# lab_fisica.net
KiCad netlist of a schematic drawn in EAGLE
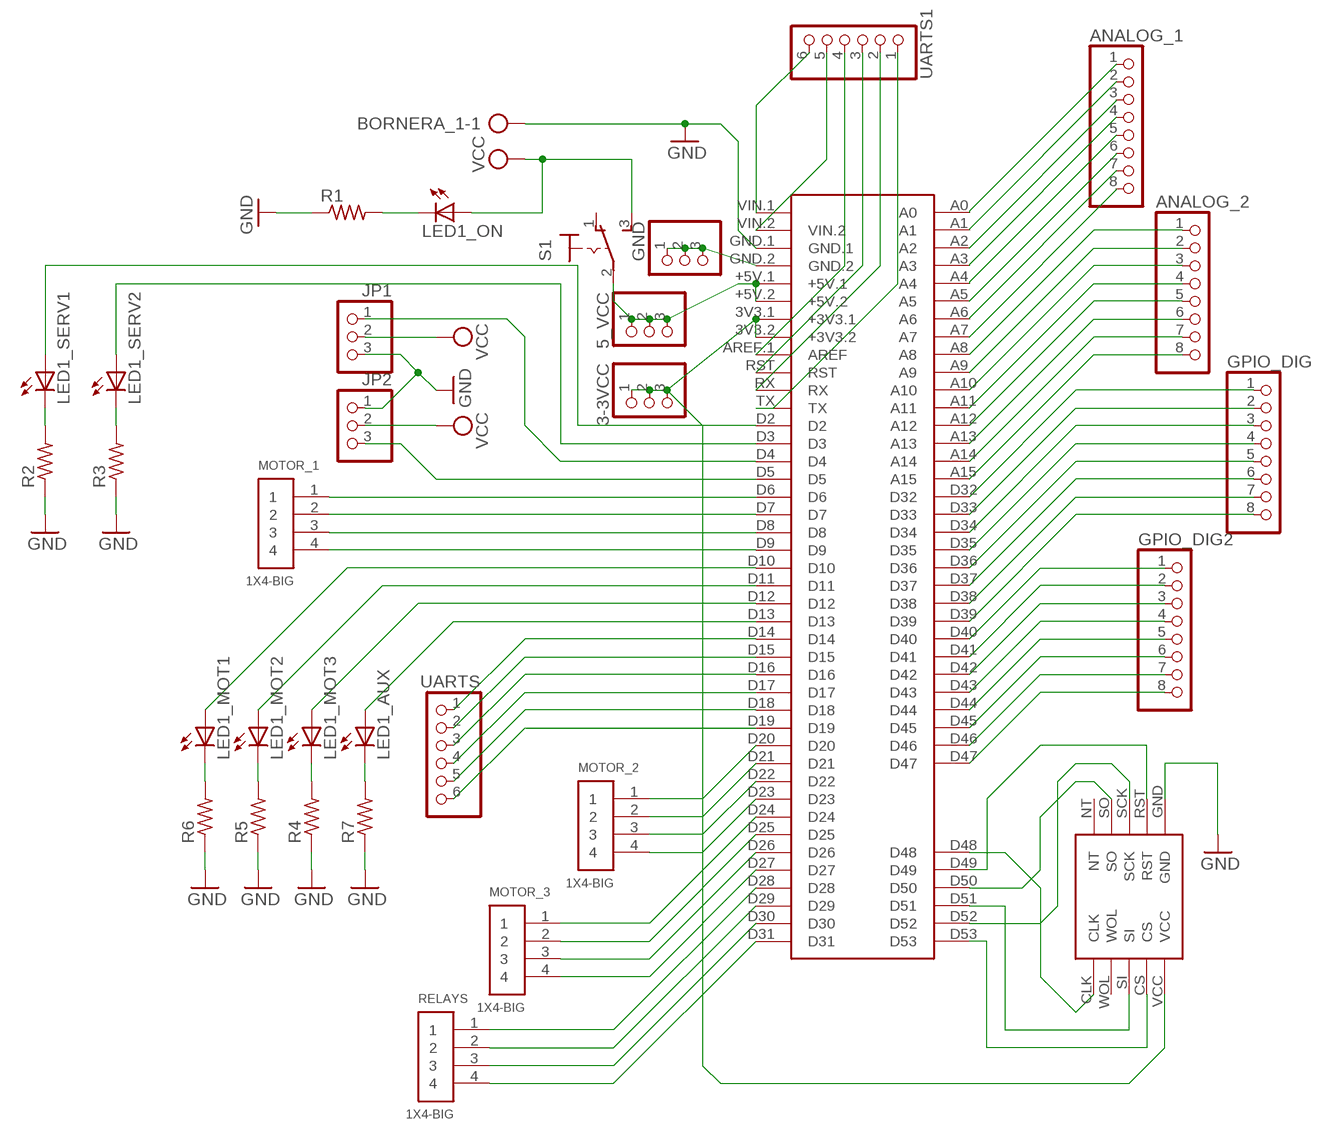
[diagram p0: schematic, sheet 1]

(export (version "E")
  (design (tool "Eeschema 10.0.6"))
  (components
    (comp (ref "3-3VCC")
      (value "PINHD-1X3")
      (footprint "eagle-import:1X03")
      (libsource (lib "eagle-import") (part "PINHD-1X3"))
    )
    (comp (ref "5_VCC")
      (value "PINHD-1X3")
      (footprint "eagle-import:1X03")
      (libsource (lib "eagle-import") (part "PINHD-1X3"))
    )
    (comp (ref "ANALOG_1")
      (value "PINHD-1X8BIG")
      (footprint "eagle-import:1X08-BIG")
      (libsource (lib "eagle-import") (part "PINHD-1X8BIG"))
    )
    (comp (ref "ANALOG_2")
      (value "PINHD-1X8BIG")
      (footprint "eagle-import:1X08-BIG")
      (libsource (lib "eagle-import") (part "PINHD-1X8BIG"))
    )
    (comp (ref "BORNERA_1")
      (value "AK300/2")
      (footprint "eagle-import:AK300_2")
      (libsource (lib "eagle-import") (part "AK300/2"))
    )
    (comp (ref "GND")
      (value "PINHD-1X3")
      (footprint "eagle-import:1X03")
      (libsource (lib "eagle-import") (part "PINHD-1X3"))
    )
    (comp (ref "GPIO_DIG")
      (value "PINHD-1X8BIG")
      (footprint "eagle-import:1X08-BIG")
      (libsource (lib "eagle-import") (part "PINHD-1X8BIG"))
    )
    (comp (ref "GPIO_DIG2")
      (value "PINHD-1X8BIG")
      (footprint "eagle-import:1X08-BIG")
      (libsource (lib "eagle-import") (part "PINHD-1X8BIG"))
    )
    (comp (ref "JP1")
      (value "PINHD-1X3")
      (footprint "eagle-import:1X03")
      (libsource (lib "eagle-import") (part "PINHD-1X3"))
    )
    (comp (ref "JP2")
      (value "PINHD-1X3")
      (footprint "eagle-import:1X03")
      (libsource (lib "eagle-import") (part "PINHD-1X3"))
    )
    (comp (ref "LED1_AUX")
      (value "LED5MM")
      (footprint "eagle-import:LED5MM")
      (libsource (lib "eagle-import") (part "LED5MM"))
    )
    (comp (ref "LED1_MOT1")
      (value "LED5MM")
      (footprint "eagle-import:LED5MM")
      (libsource (lib "eagle-import") (part "LED5MM"))
    )
    (comp (ref "LED1_MOT2")
      (value "LED5MM")
      (footprint "eagle-import:LED5MM")
      (libsource (lib "eagle-import") (part "LED5MM"))
    )
    (comp (ref "LED1_MOT3")
      (value "LED5MM")
      (footprint "eagle-import:LED5MM")
      (libsource (lib "eagle-import") (part "LED5MM"))
    )
    (comp (ref "LED1_ON")
      (value "LED5MM")
      (footprint "eagle-import:LED5MM")
      (libsource (lib "eagle-import") (part "LED5MM"))
    )
    (comp (ref "LED1_SERV1")
      (value "LED5MM")
      (footprint "eagle-import:LED5MM")
      (libsource (lib "eagle-import") (part "LED5MM"))
    )
    (comp (ref "LED1_SERV2")
      (value "LED5MM")
      (footprint "eagle-import:LED5MM")
      (libsource (lib "eagle-import") (part "LED5MM"))
    )
    (comp (ref "MODULO_ETHERNET")
      (value "ENC28J60")
      (footprint "eagle-import:ENC28J60")
      (libsource (lib "eagle-import") (part "ENC28J60"))
    )
    (comp (ref "MOTOR_1")
      (value "1X4-BIG")
      (footprint "eagle-import:1X04-BIG")
      (libsource (lib "eagle-import") (part "1X4-BIG"))
    )
    (comp (ref "MOTOR_2")
      (value "1X4-BIG")
      (footprint "eagle-import:1X04-BIG")
      (libsource (lib "eagle-import") (part "1X4-BIG"))
    )
    (comp (ref "MOTOR_3")
      (value "1X4-BIG")
      (footprint "eagle-import:1X04-BIG")
      (libsource (lib "eagle-import") (part "1X4-BIG"))
    )
    (comp (ref "R1")
      (value "R-US_R0805")
      (footprint "eagle-import:R0805")
      (libsource (lib "eagle-import") (part "R-US_R0805"))
    )
    (comp (ref "R2")
      (value "R-US_R0805")
      (footprint "eagle-import:R0805")
      (libsource (lib "eagle-import") (part "R-US_R0805"))
    )
    (comp (ref "R3")
      (value "R-US_R0805")
      (footprint "eagle-import:R0805")
      (libsource (lib "eagle-import") (part "R-US_R0805"))
    )
    (comp (ref "R4")
      (value "R-US_R0805")
      (footprint "eagle-import:R0805")
      (libsource (lib "eagle-import") (part "R-US_R0805"))
    )
    (comp (ref "R5")
      (value "R-US_R0805")
      (footprint "eagle-import:R0805")
      (libsource (lib "eagle-import") (part "R-US_R0805"))
    )
    (comp (ref "R6")
      (value "R-US_R0805")
      (footprint "eagle-import:R0805")
      (libsource (lib "eagle-import") (part "R-US_R0805"))
    )
    (comp (ref "R7")
      (value "R-US_R0805")
      (footprint "eagle-import:R0805")
      (libsource (lib "eagle-import") (part "R-US_R0805"))
    )
    (comp (ref "RELAYS")
      (value "1X4-BIG")
      (footprint "eagle-import:1X04-BIG")
      (libsource (lib "eagle-import") (part "1X4-BIG"))
    )
    (comp (ref "S1")
      (value "320-916")
      (footprint "eagle-import:320-916")
      (libsource (lib "eagle-import") (part "320-916"))
    )
    (comp (ref "U$1")
      (value "MEGA2560_MIKRO")
      (footprint "eagle-import:MEGA2560_MIKRO")
      (libsource (lib "eagle-import") (part "MEGA2560_MIKRO"))
    )
    (comp (ref "UARTS")
      (value "PINHD-1X6B")
      (footprint "eagle-import:1X06-BIG")
      (libsource (lib "eagle-import") (part "PINHD-1X6B"))
    )
    (comp (ref "UARTS1")
      (value "PINHD-1X6B")
      (footprint "eagle-import:1X06-BIG")
      (libsource (lib "eagle-import") (part "PINHD-1X6B"))
    )
  )
  (nets
    (net (code "1") (name "GND") (class "Default")
      (node (ref "BORNERA_1") (pin "1") (pinfunction "KL_1") (pintype "passive"))
      (node (ref "JP1") (pin "3") (pinfunction "3_3") (pintype "passive"))
      (node (ref "JP2") (pin "1") (pinfunction "1_1") (pintype "passive"))
      (node (ref "MODULO_ETHERNET") (pin "GND") (pinfunction "GND_GND") (pintype "bidirectional"))
      (node (ref "R1") (pin "1") (pinfunction "1_1") (pintype "passive"))
      (node (ref "R2") (pin "1") (pinfunction "1_1") (pintype "passive"))
      (node (ref "R3") (pin "1") (pinfunction "1_1") (pintype "passive"))
      (node (ref "R4") (pin "1") (pinfunction "1_1") (pintype "passive"))
      (node (ref "R5") (pin "1") (pinfunction "1_1") (pintype "passive"))
      (node (ref "R6") (pin "1") (pinfunction "1_1") (pintype "passive"))
      (node (ref "R7") (pin "1") (pinfunction "1_1") (pintype "passive"))
      (node (ref "U$1") (pin "GND.1") (pinfunction "GND.1_GND.1") (pintype "bidirectional"))
    )
    (net (code "2") (name "Net-(ANALOG_1-Pad1)") (class "Default")
      (node (ref "ANALOG_1") (pin "1") (pinfunction "1_1") (pintype "passive"))
      (node (ref "U$1") (pin "A0") (pinfunction "A0_A0") (pintype "bidirectional"))
    )
    (net (code "3") (name "Net-(ANALOG_1-Pad2)") (class "Default")
      (node (ref "ANALOG_1") (pin "2") (pinfunction "2_2") (pintype "passive"))
      (node (ref "U$1") (pin "A1") (pinfunction "A1_A1") (pintype "bidirectional"))
    )
    (net (code "4") (name "Net-(ANALOG_1-Pad3)") (class "Default")
      (node (ref "ANALOG_1") (pin "3") (pinfunction "3_3") (pintype "passive"))
      (node (ref "U$1") (pin "A2") (pinfunction "A2_A2") (pintype "bidirectional"))
    )
    (net (code "5") (name "Net-(ANALOG_1-Pad4)") (class "Default")
      (node (ref "ANALOG_1") (pin "4") (pinfunction "4_4") (pintype "passive"))
      (node (ref "U$1") (pin "A3") (pinfunction "A3_A3") (pintype "bidirectional"))
    )
    (net (code "6") (name "Net-(ANALOG_1-Pad5)") (class "Default")
      (node (ref "ANALOG_1") (pin "5") (pinfunction "5_5") (pintype "passive"))
      (node (ref "U$1") (pin "A4") (pinfunction "A4_A4") (pintype "bidirectional"))
    )
    (net (code "7") (name "Net-(ANALOG_1-Pad6)") (class "Default")
      (node (ref "ANALOG_1") (pin "6") (pinfunction "6_6") (pintype "passive"))
      (node (ref "U$1") (pin "A5") (pinfunction "A5_A5") (pintype "bidirectional"))
    )
    (net (code "8") (name "Net-(ANALOG_1-Pad7)") (class "Default")
      (node (ref "ANALOG_1") (pin "7") (pinfunction "7_7") (pintype "passive"))
      (node (ref "U$1") (pin "A6") (pinfunction "A6_A6") (pintype "bidirectional"))
    )
    (net (code "9") (name "Net-(ANALOG_1-Pad8)") (class "Default")
      (node (ref "ANALOG_1") (pin "8") (pinfunction "8_8") (pintype "passive"))
      (node (ref "U$1") (pin "A7") (pinfunction "A7_A7") (pintype "bidirectional"))
    )
    (net (code "10") (name "Net-(ANALOG_2-Pad1)") (class "Default")
      (node (ref "ANALOG_2") (pin "1") (pinfunction "1_1") (pintype "passive"))
      (node (ref "U$1") (pin "A8") (pinfunction "A8_A8") (pintype "bidirectional"))
    )
    (net (code "11") (name "Net-(ANALOG_2-Pad2)") (class "Default")
      (node (ref "ANALOG_2") (pin "2") (pinfunction "2_2") (pintype "passive"))
      (node (ref "U$1") (pin "A9") (pinfunction "A9_A9") (pintype "bidirectional"))
    )
    (net (code "12") (name "Net-(ANALOG_2-Pad3)") (class "Default")
      (node (ref "ANALOG_2") (pin "3") (pinfunction "3_3") (pintype "passive"))
      (node (ref "U$1") (pin "A10") (pinfunction "A10_A10") (pintype "bidirectional"))
    )
    (net (code "13") (name "Net-(ANALOG_2-Pad4)") (class "Default")
      (node (ref "ANALOG_2") (pin "4") (pinfunction "4_4") (pintype "passive"))
      (node (ref "U$1") (pin "A11") (pinfunction "A11_A11") (pintype "bidirectional"))
    )
    (net (code "14") (name "Net-(ANALOG_2-Pad5)") (class "Default")
      (node (ref "ANALOG_2") (pin "5") (pinfunction "5_5") (pintype "passive"))
      (node (ref "U$1") (pin "A12") (pinfunction "A12_A12") (pintype "bidirectional"))
    )
    (net (code "15") (name "Net-(ANALOG_2-Pad6)") (class "Default")
      (node (ref "ANALOG_2") (pin "6") (pinfunction "6_6") (pintype "passive"))
      (node (ref "U$1") (pin "A13") (pinfunction "A13_A13") (pintype "bidirectional"))
    )
    (net (code "16") (name "Net-(ANALOG_2-Pad7)") (class "Default")
      (node (ref "ANALOG_2") (pin "7") (pinfunction "7_7") (pintype "passive"))
      (node (ref "U$1") (pin "A14") (pinfunction "A14_A14") (pintype "bidirectional"))
    )
    (net (code "17") (name "Net-(ANALOG_2-Pad8)") (class "Default")
      (node (ref "ANALOG_2") (pin "8") (pinfunction "8_8") (pintype "passive"))
      (node (ref "U$1") (pin "A15") (pinfunction "A15_A15") (pintype "bidirectional"))
    )
    (net (code "18") (name "Net-(GND-Pad1)") (class "Default")
      (node (ref "GND") (pin "1") (pinfunction "1_1") (pintype "passive"))
      (node (ref "GND") (pin "2") (pinfunction "2_2") (pintype "passive"))
      (node (ref "GND") (pin "3") (pinfunction "3_3") (pintype "passive"))
      (node (ref "U$1") (pin "GND.2") (pinfunction "GND.2_GND.2") (pintype "bidirectional"))
    )
    (net (code "19") (name "Net-(GPIO_DIG-Pad1)") (class "Default")
      (node (ref "GPIO_DIG") (pin "1") (pinfunction "1_1") (pintype "passive"))
      (node (ref "U$1") (pin "D32") (pinfunction "D32_D32") (pintype "bidirectional"))
    )
    (net (code "20") (name "Net-(GPIO_DIG-Pad2)") (class "Default")
      (node (ref "GPIO_DIG") (pin "2") (pinfunction "2_2") (pintype "passive"))
      (node (ref "U$1") (pin "D33") (pinfunction "D33_D33") (pintype "bidirectional"))
    )
    (net (code "21") (name "Net-(GPIO_DIG-Pad3)") (class "Default")
      (node (ref "GPIO_DIG") (pin "3") (pinfunction "3_3") (pintype "passive"))
      (node (ref "U$1") (pin "D34") (pinfunction "D34_D34") (pintype "bidirectional"))
    )
    (net (code "22") (name "Net-(GPIO_DIG-Pad4)") (class "Default")
      (node (ref "GPIO_DIG") (pin "4") (pinfunction "4_4") (pintype "passive"))
      (node (ref "U$1") (pin "D35") (pinfunction "D35_D35") (pintype "bidirectional"))
    )
    (net (code "23") (name "Net-(GPIO_DIG-Pad5)") (class "Default")
      (node (ref "GPIO_DIG") (pin "5") (pinfunction "5_5") (pintype "passive"))
      (node (ref "U$1") (pin "D36") (pinfunction "D36_D36") (pintype "bidirectional"))
    )
    (net (code "24") (name "Net-(GPIO_DIG-Pad6)") (class "Default")
      (node (ref "GPIO_DIG") (pin "6") (pinfunction "6_6") (pintype "passive"))
      (node (ref "U$1") (pin "D37") (pinfunction "D37_D37") (pintype "bidirectional"))
    )
    (net (code "25") (name "Net-(GPIO_DIG-Pad7)") (class "Default")
      (node (ref "GPIO_DIG") (pin "7") (pinfunction "7_7") (pintype "passive"))
      (node (ref "U$1") (pin "D38") (pinfunction "D38_D38") (pintype "bidirectional"))
    )
    (net (code "26") (name "Net-(GPIO_DIG-Pad8)") (class "Default")
      (node (ref "GPIO_DIG") (pin "8") (pinfunction "8_8") (pintype "passive"))
      (node (ref "U$1") (pin "D39") (pinfunction "D39_D39") (pintype "bidirectional"))
    )
    (net (code "27") (name "Net-(GPIO_DIG2-Pad1)") (class "Default")
      (node (ref "GPIO_DIG2") (pin "1") (pinfunction "1_1") (pintype "passive"))
      (node (ref "U$1") (pin "D40") (pinfunction "D40_D40") (pintype "bidirectional"))
    )
    (net (code "28") (name "Net-(GPIO_DIG2-Pad2)") (class "Default")
      (node (ref "GPIO_DIG2") (pin "2") (pinfunction "2_2") (pintype "passive"))
      (node (ref "U$1") (pin "D41") (pinfunction "D41_D41") (pintype "bidirectional"))
    )
    (net (code "29") (name "Net-(GPIO_DIG2-Pad3)") (class "Default")
      (node (ref "GPIO_DIG2") (pin "3") (pinfunction "3_3") (pintype "passive"))
      (node (ref "U$1") (pin "D42") (pinfunction "D42_D42") (pintype "bidirectional"))
    )
    (net (code "30") (name "Net-(GPIO_DIG2-Pad4)") (class "Default")
      (node (ref "GPIO_DIG2") (pin "4") (pinfunction "4_4") (pintype "passive"))
      (node (ref "U$1") (pin "D43") (pinfunction "D43_D43") (pintype "bidirectional"))
    )
    (net (code "31") (name "Net-(GPIO_DIG2-Pad5)") (class "Default")
      (node (ref "GPIO_DIG2") (pin "5") (pinfunction "5_5") (pintype "passive"))
      (node (ref "U$1") (pin "D44") (pinfunction "D44_D44") (pintype "bidirectional"))
    )
    (net (code "32") (name "Net-(GPIO_DIG2-Pad6)") (class "Default")
      (node (ref "GPIO_DIG2") (pin "6") (pinfunction "6_6") (pintype "passive"))
      (node (ref "U$1") (pin "D45") (pinfunction "D45_D45") (pintype "bidirectional"))
    )
    (net (code "33") (name "Net-(GPIO_DIG2-Pad7)") (class "Default")
      (node (ref "GPIO_DIG2") (pin "7") (pinfunction "7_7") (pintype "passive"))
      (node (ref "U$1") (pin "D46") (pinfunction "D46_D46") (pintype "bidirectional"))
    )
    (net (code "34") (name "Net-(GPIO_DIG2-Pad8)") (class "Default")
      (node (ref "GPIO_DIG2") (pin "8") (pinfunction "8_8") (pintype "passive"))
      (node (ref "U$1") (pin "D47") (pinfunction "D47_D47") (pintype "bidirectional"))
    )
    (net (code "35") (name "Net-(JP1-Pad1)") (class "Default")
      (node (ref "JP1") (pin "1") (pinfunction "1_1") (pintype "passive"))
      (node (ref "U$1") (pin "D4") (pinfunction "D4_D4") (pintype "bidirectional"))
    )
    (net (code "36") (name "Net-(JP2-Pad3)") (class "Default")
      (node (ref "JP2") (pin "3") (pinfunction "3_3") (pintype "passive"))
      (node (ref "U$1") (pin "D5") (pinfunction "D5_D5") (pintype "bidirectional"))
    )
    (net (code "37") (name "Net-(LED1_AUX-C)") (class "Default")
      (node (ref "LED1_AUX") (pin "K") (pinfunction "C_K") (pintype "passive"))
      (node (ref "R7") (pin "2") (pinfunction "2_2") (pintype "passive"))
    )
    (net (code "38") (name "Net-(LED1_AUX-PadA)") (class "Default")
      (node (ref "LED1_AUX") (pin "A") (pinfunction "A_A") (pintype "passive"))
      (node (ref "U$1") (pin "D13") (pinfunction "D13_D13") (pintype "bidirectional"))
    )
    (net (code "39") (name "Net-(LED1_MOT1-C)") (class "Default")
      (node (ref "LED1_MOT1") (pin "K") (pinfunction "C_K") (pintype "passive"))
      (node (ref "R6") (pin "2") (pinfunction "2_2") (pintype "passive"))
    )
    (net (code "40") (name "Net-(LED1_MOT1-PadA)") (class "Default")
      (node (ref "LED1_MOT1") (pin "A") (pinfunction "A_A") (pintype "passive"))
      (node (ref "U$1") (pin "D10") (pinfunction "D10_D10") (pintype "bidirectional"))
    )
    (net (code "41") (name "Net-(LED1_MOT2-C)") (class "Default")
      (node (ref "LED1_MOT2") (pin "K") (pinfunction "C_K") (pintype "passive"))
      (node (ref "R5") (pin "2") (pinfunction "2_2") (pintype "passive"))
    )
    (net (code "42") (name "Net-(LED1_MOT2-PadA)") (class "Default")
      (node (ref "LED1_MOT2") (pin "A") (pinfunction "A_A") (pintype "passive"))
      (node (ref "U$1") (pin "D11") (pinfunction "D11_D11") (pintype "bidirectional"))
    )
    (net (code "43") (name "Net-(LED1_MOT3-C)") (class "Default")
      (node (ref "LED1_MOT3") (pin "K") (pinfunction "C_K") (pintype "passive"))
      (node (ref "R4") (pin "2") (pinfunction "2_2") (pintype "passive"))
    )
    (net (code "44") (name "Net-(LED1_MOT3-PadA)") (class "Default")
      (node (ref "LED1_MOT3") (pin "A") (pinfunction "A_A") (pintype "passive"))
      (node (ref "U$1") (pin "D12") (pinfunction "D12_D12") (pintype "bidirectional"))
    )
    (net (code "45") (name "Net-(LED1_ON-C)") (class "Default")
      (node (ref "LED1_ON") (pin "K") (pinfunction "C_K") (pintype "passive"))
      (node (ref "R1") (pin "2") (pinfunction "2_2") (pintype "passive"))
    )
    (net (code "46") (name "Net-(LED1_SERV1-C)") (class "Default")
      (node (ref "LED1_SERV1") (pin "K") (pinfunction "C_K") (pintype "passive"))
      (node (ref "R2") (pin "2") (pinfunction "2_2") (pintype "passive"))
    )
    (net (code "47") (name "Net-(LED1_SERV1-PadA)") (class "Default")
      (node (ref "LED1_SERV1") (pin "A") (pinfunction "A_A") (pintype "passive"))
      (node (ref "U$1") (pin "D2") (pinfunction "D2_D2") (pintype "bidirectional"))
    )
    (net (code "48") (name "Net-(LED1_SERV2-C)") (class "Default")
      (node (ref "LED1_SERV2") (pin "K") (pinfunction "C_K") (pintype "passive"))
      (node (ref "R3") (pin "2") (pinfunction "2_2") (pintype "passive"))
    )
    (net (code "49") (name "Net-(LED1_SERV2-PadA)") (class "Default")
      (node (ref "LED1_SERV2") (pin "A") (pinfunction "A_A") (pintype "passive"))
      (node (ref "U$1") (pin "D3") (pinfunction "D3_D3") (pintype "bidirectional"))
    )
    (net (code "50") (name "Net-(MODULO_ETHERNET-PadCLK)") (class "Default")
      (node (ref "MODULO_ETHERNET") (pin "CLK") (pinfunction "CLK_CLK") (pintype "bidirectional"))
      (node (ref "U$1") (pin "D48") (pinfunction "D48_D48") (pintype "bidirectional"))
    )
    (net (code "51") (name "Net-(MODULO_ETHERNET-PadCS)") (class "Default")
      (node (ref "MODULO_ETHERNET") (pin "CS") (pinfunction "CS_CS") (pintype "bidirectional"))
      (node (ref "U$1") (pin "D53") (pinfunction "D53_D53") (pintype "bidirectional"))
    )
    (net (code "52") (name "Net-(MODULO_ETHERNET-PadRST)") (class "Default")
      (node (ref "MODULO_ETHERNET") (pin "RST") (pinfunction "RST_RST") (pintype "bidirectional"))
      (node (ref "U$1") (pin "D49") (pinfunction "D49_D49") (pintype "bidirectional"))
    )
    (net (code "53") (name "Net-(MODULO_ETHERNET-PadSCK)") (class "Default")
      (node (ref "MODULO_ETHERNET") (pin "SCK") (pinfunction "SCK_SCK") (pintype "bidirectional"))
      (node (ref "U$1") (pin "D52") (pinfunction "D52_D52") (pintype "bidirectional"))
    )
    (net (code "54") (name "Net-(MODULO_ETHERNET-PadSI)") (class "Default")
      (node (ref "MODULO_ETHERNET") (pin "SI") (pinfunction "SI_SI") (pintype "bidirectional"))
      (node (ref "U$1") (pin "D51") (pinfunction "D51_D51") (pintype "bidirectional"))
    )
    (net (code "55") (name "Net-(MODULO_ETHERNET-PadSO)") (class "Default")
      (node (ref "MODULO_ETHERNET") (pin "SO") (pinfunction "SO_SO") (pintype "bidirectional"))
      (node (ref "U$1") (pin "D50") (pinfunction "D50_D50") (pintype "bidirectional"))
    )
    (net (code "56") (name "Net-(MOTOR_1-Pad1)") (class "Default")
      (node (ref "MOTOR_1") (pin "1") (pinfunction "1_1") (pintype "bidirectional"))
      (node (ref "U$1") (pin "D6") (pinfunction "D6_D6") (pintype "bidirectional"))
    )
    (net (code "57") (name "Net-(MOTOR_1-Pad2)") (class "Default")
      (node (ref "MOTOR_1") (pin "2") (pinfunction "2_2") (pintype "bidirectional"))
      (node (ref "U$1") (pin "D7") (pinfunction "D7_D7") (pintype "bidirectional"))
    )
    (net (code "58") (name "Net-(MOTOR_1-Pad3)") (class "Default")
      (node (ref "MOTOR_1") (pin "3") (pinfunction "3_3") (pintype "bidirectional"))
      (node (ref "U$1") (pin "D8") (pinfunction "D8_D8") (pintype "bidirectional"))
    )
    (net (code "59") (name "Net-(MOTOR_1-Pad4)") (class "Default")
      (node (ref "MOTOR_1") (pin "4") (pinfunction "4_4") (pintype "bidirectional"))
      (node (ref "U$1") (pin "D9") (pinfunction "D9_D9") (pintype "bidirectional"))
    )
    (net (code "60") (name "Net-(MOTOR_2-Pad1)") (class "Default")
      (node (ref "MOTOR_2") (pin "1") (pinfunction "1_1") (pintype "bidirectional"))
      (node (ref "U$1") (pin "D20") (pinfunction "D20_D20") (pintype "bidirectional"))
    )
    (net (code "61") (name "Net-(MOTOR_2-Pad2)") (class "Default")
      (node (ref "MOTOR_2") (pin "2") (pinfunction "2_2") (pintype "bidirectional"))
      (node (ref "U$1") (pin "D21") (pinfunction "D21_D21") (pintype "bidirectional"))
    )
    (net (code "62") (name "Net-(MOTOR_2-Pad3)") (class "Default")
      (node (ref "MOTOR_2") (pin "3") (pinfunction "3_3") (pintype "bidirectional"))
      (node (ref "U$1") (pin "D22") (pinfunction "D22_D22") (pintype "bidirectional"))
    )
    (net (code "63") (name "Net-(MOTOR_2-Pad4)") (class "Default")
      (node (ref "MOTOR_2") (pin "4") (pinfunction "4_4") (pintype "bidirectional"))
      (node (ref "U$1") (pin "D23") (pinfunction "D23_D23") (pintype "bidirectional"))
    )
    (net (code "64") (name "Net-(MOTOR_3-Pad1)") (class "Default")
      (node (ref "MOTOR_3") (pin "1") (pinfunction "1_1") (pintype "bidirectional"))
      (node (ref "U$1") (pin "D24") (pinfunction "D24_D24") (pintype "bidirectional"))
    )
    (net (code "65") (name "Net-(MOTOR_3-Pad2)") (class "Default")
      (node (ref "MOTOR_3") (pin "2") (pinfunction "2_2") (pintype "bidirectional"))
      (node (ref "U$1") (pin "D25") (pinfunction "D25_D25") (pintype "bidirectional"))
    )
    (net (code "66") (name "Net-(MOTOR_3-Pad3)") (class "Default")
      (node (ref "MOTOR_3") (pin "3") (pinfunction "3_3") (pintype "bidirectional"))
      (node (ref "U$1") (pin "D26") (pinfunction "D26_D26") (pintype "bidirectional"))
    )
    (net (code "67") (name "Net-(MOTOR_3-Pad4)") (class "Default")
      (node (ref "MOTOR_3") (pin "4") (pinfunction "4_4") (pintype "bidirectional"))
      (node (ref "U$1") (pin "D27") (pinfunction "D27_D27") (pintype "bidirectional"))
    )
    (net (code "68") (name "Net-(RELAYS-Pad1)") (class "Default")
      (node (ref "RELAYS") (pin "1") (pinfunction "1_1") (pintype "bidirectional"))
      (node (ref "U$1") (pin "D28") (pinfunction "D28_D28") (pintype "bidirectional"))
    )
    (net (code "69") (name "Net-(RELAYS-Pad2)") (class "Default")
      (node (ref "RELAYS") (pin "2") (pinfunction "2_2") (pintype "bidirectional"))
      (node (ref "U$1") (pin "D29") (pinfunction "D29_D29") (pintype "bidirectional"))
    )
    (net (code "70") (name "Net-(RELAYS-Pad3)") (class "Default")
      (node (ref "RELAYS") (pin "3") (pinfunction "3_3") (pintype "bidirectional"))
      (node (ref "U$1") (pin "D30") (pinfunction "D30_D30") (pintype "bidirectional"))
    )
    (net (code "71") (name "Net-(RELAYS-Pad4)") (class "Default")
      (node (ref "RELAYS") (pin "4") (pinfunction "4_4") (pintype "bidirectional"))
      (node (ref "U$1") (pin "D31") (pinfunction "D31_D31") (pintype "bidirectional"))
    )
    (net (code "72") (name "Net-(S1-P)") (class "Default")
      (node (ref "5_VCC") (pin "1") (pinfunction "1_1") (pintype "passive"))
      (node (ref "5_VCC") (pin "2") (pinfunction "2_2") (pintype "passive"))
      (node (ref "5_VCC") (pin "3") (pinfunction "3_3") (pintype "passive"))
      (node (ref "S1") (pin "2") (pinfunction "P_2") (pintype "passive"))
      (node (ref "U$1") (pin "+5V.1") (pinfunction "+5V.1_+5V.1") (pintype "bidirectional"))
      (node (ref "U$1") (pin "+5V.2") (pinfunction "+5V.2_+5V.2") (pintype "bidirectional"))
    )
    (net (code "73") (name "Net-(U$1-+3V3.1)") (class "Default")
      (node (ref "3-3VCC") (pin "1") (pinfunction "1_1") (pintype "passive"))
      (node (ref "3-3VCC") (pin "2") (pinfunction "2_2") (pintype "passive"))
      (node (ref "3-3VCC") (pin "3") (pinfunction "3_3") (pintype "passive"))
      (node (ref "MODULO_ETHERNET") (pin "VCC") (pinfunction "VCC_VCC") (pintype "bidirectional"))
      (node (ref "U$1") (pin "3V3.1") (pinfunction "+3V3.1_3V3.1") (pintype "bidirectional"))
      (node (ref "U$1") (pin "3V3.2") (pinfunction "+3V3.2_3V3.2") (pintype "bidirectional"))
    )
    (net (code "74") (name "Net-(U$1-AREF)") (class "Default")
      (node (ref "U$1") (pin "AREF.1") (pinfunction "AREF_AREF.1") (pintype "bidirectional"))
      (node (ref "UARTS1") (pin "4") (pinfunction "4_4") (pintype "passive"))
    )
    (net (code "75") (name "Net-(U$1-PadD14)") (class "Default")
      (node (ref "U$1") (pin "D14") (pinfunction "D14_D14") (pintype "bidirectional"))
      (node (ref "UARTS") (pin "1") (pinfunction "1_1") (pintype "passive"))
    )
    (net (code "76") (name "Net-(U$1-PadD15)") (class "Default")
      (node (ref "U$1") (pin "D15") (pinfunction "D15_D15") (pintype "bidirectional"))
      (node (ref "UARTS") (pin "2") (pinfunction "2_2") (pintype "passive"))
    )
    (net (code "77") (name "Net-(U$1-PadD16)") (class "Default")
      (node (ref "U$1") (pin "D16") (pinfunction "D16_D16") (pintype "bidirectional"))
      (node (ref "UARTS") (pin "3") (pinfunction "3_3") (pintype "passive"))
    )
    (net (code "78") (name "Net-(U$1-PadD17)") (class "Default")
      (node (ref "U$1") (pin "D17") (pinfunction "D17_D17") (pintype "bidirectional"))
      (node (ref "UARTS") (pin "4") (pinfunction "4_4") (pintype "passive"))
    )
    (net (code "79") (name "Net-(U$1-PadD18)") (class "Default")
      (node (ref "U$1") (pin "D18") (pinfunction "D18_D18") (pintype "bidirectional"))
      (node (ref "UARTS") (pin "5") (pinfunction "5_5") (pintype "passive"))
    )
    (net (code "80") (name "Net-(U$1-PadD19)") (class "Default")
      (node (ref "U$1") (pin "D19") (pinfunction "D19_D19") (pintype "bidirectional"))
      (node (ref "UARTS") (pin "6") (pinfunction "6_6") (pintype "passive"))
    )
    (net (code "81") (name "Net-(U$1-PadRST)") (class "Default")
      (node (ref "U$1") (pin "RST") (pinfunction "RST_RST") (pintype "bidirectional"))
      (node (ref "UARTS1") (pin "3") (pinfunction "3_3") (pintype "passive"))
    )
    (net (code "82") (name "Net-(U$1-PadRX)") (class "Default")
      (node (ref "U$1") (pin "RX") (pinfunction "RX_RX") (pintype "bidirectional"))
      (node (ref "UARTS1") (pin "2") (pinfunction "2_2") (pintype "passive"))
    )
    (net (code "83") (name "Net-(U$1-PadTX)") (class "Default")
      (node (ref "U$1") (pin "TX") (pinfunction "TX_TX") (pintype "bidirectional"))
      (node (ref "UARTS1") (pin "1") (pinfunction "1_1") (pintype "passive"))
    )
    (net (code "84") (name "Net-(U$1-PadVIN.1)") (class "Default")
      (node (ref "U$1") (pin "VIN.1") (pinfunction "VIN.1_VIN.1") (pintype "bidirectional"))
      (node (ref "UARTS1") (pin "6") (pinfunction "6_6") (pintype "passive"))
    )
    (net (code "85") (name "Net-(U$1-PadVIN.2)") (class "Default")
      (node (ref "U$1") (pin "VIN.2") (pinfunction "VIN.2_VIN.2") (pintype "bidirectional"))
      (node (ref "UARTS1") (pin "5") (pinfunction "5_5") (pintype "passive"))
    )
    (net (code "86") (name "VCC") (class "Default")
      (node (ref "JP1") (pin "2") (pinfunction "2_2") (pintype "passive"))
      (node (ref "JP2") (pin "2") (pinfunction "2_2") (pintype "passive"))
      (node (ref "LED1_ON") (pin "A") (pinfunction "A_A") (pintype "passive"))
      (node (ref "S1") (pin "3") (pinfunction "S_3") (pintype "passive"))
    )
    (net (code "87") (name "unconnected-(MODULO_ETHERNET-PadNT)") (class "Default")
      (node (ref "MODULO_ETHERNET") (pin "NT") (pinfunction "NT_NT") (pintype "bidirectional"))
    )
    (net (code "88") (name "unconnected-(MODULO_ETHERNET-PadWOL)") (class "Default")
      (node (ref "MODULO_ETHERNET") (pin "WOL") (pinfunction "WOL_WOL") (pintype "bidirectional"))
    )
    (net (code "89") (name "unconnected-(S1-O-Pad1)") (class "Default")
      (node (ref "S1") (pin "1") (pinfunction "O_1") (pintype "passive"))
    )
  )
)
